# CH32V307RCT6-R1.net
KiCad netlist of a schematic drawn in Altium Designer
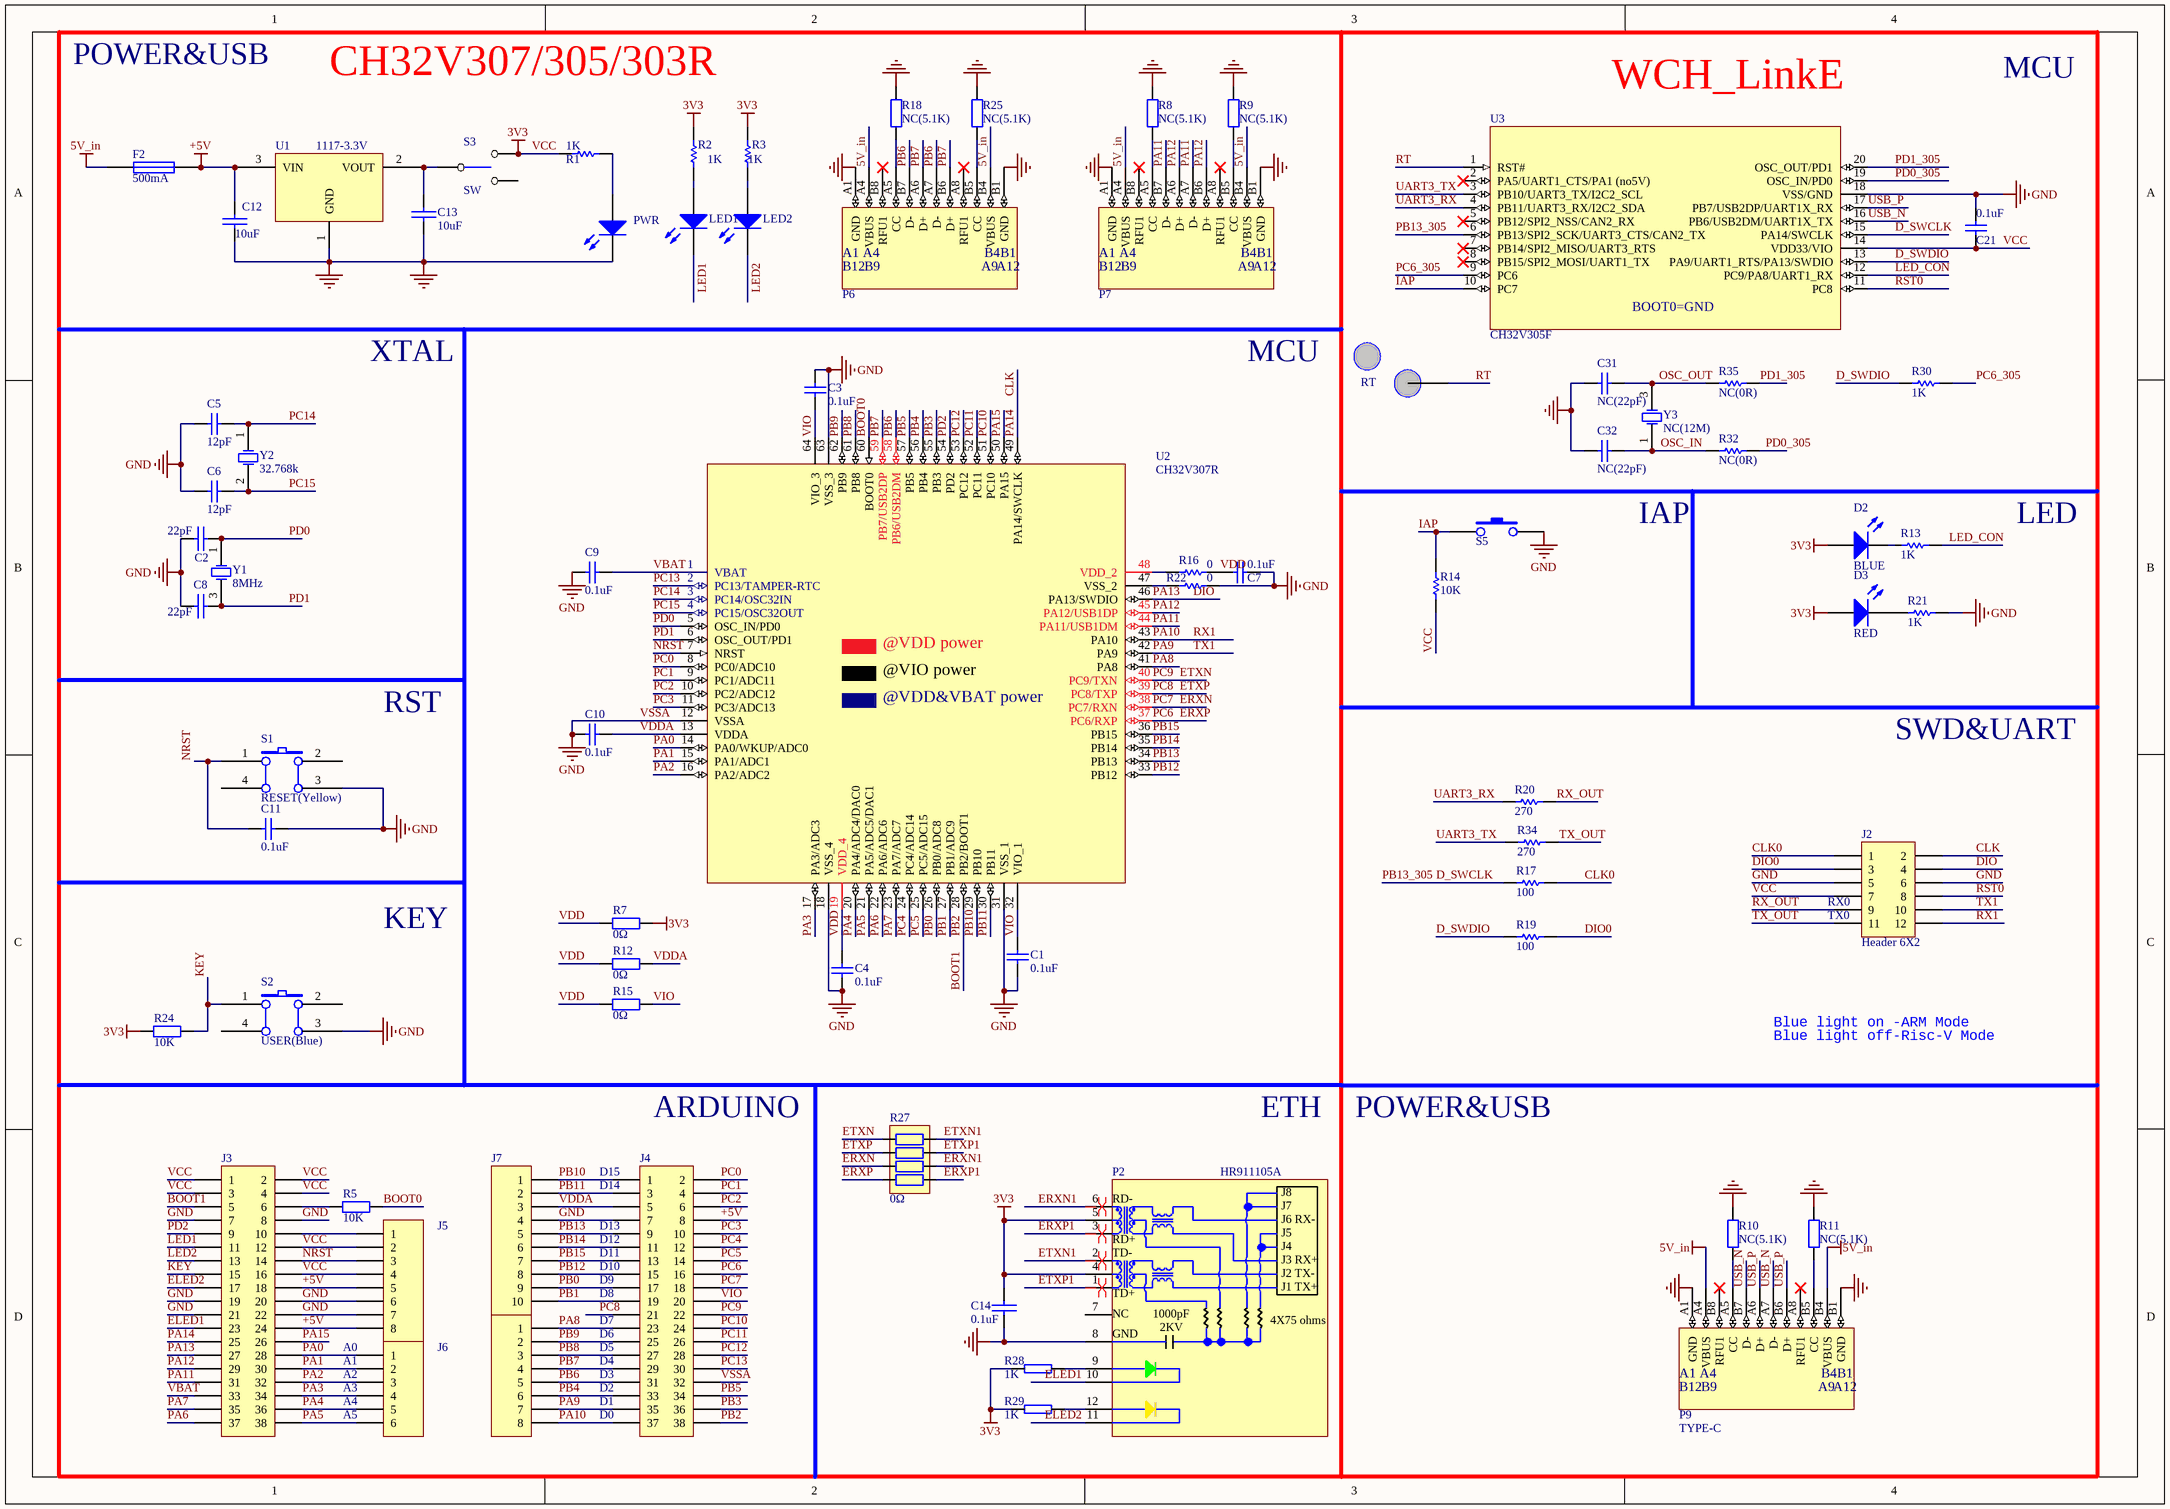
[diagram p0: CH32V307RCT6-R1.SchDoc]

(export (version "E")
  (design (tool "Eeschema 10.0.6"))
  (components
    (comp (ref "C1")
      (value "0.1uF")
      (footprint "0603_C")
      (description "Capacitor")
      (libsource (lib "Miscellaneous Devices") (part "Cap"))
    )
    (comp (ref "C2")
      (value "22pF")
      (footprint "0603_C")
      (description "Capacitor")
      (libsource (lib "*") (part "CAP"))
    )
    (comp (ref "C3")
      (value "0.1uF")
      (footprint "0603_C")
      (description "Capacitor")
      (libsource (lib "Miscellaneous Devices") (part "Cap"))
    )
    (comp (ref "C4")
      (value "0.1uF")
      (footprint "0603_C")
      (description "Capacitor")
      (libsource (lib "Miscellaneous Devices") (part "Cap"))
    )
    (comp (ref "C5")
      (value "12pF")
      (footprint "0603_C")
      (description "Capacitor")
      (libsource (lib "Miscellaneous Devices") (part "Cap"))
    )
    (comp (ref "C6")
      (value "12pF")
      (footprint "0603_C")
      (description "Capacitor")
      (libsource (lib "Miscellaneous Devices") (part "Cap"))
    )
    (comp (ref "C7")
      (value "0.1uF")
      (footprint "0603_C")
      (description "Capacitor")
      (libsource (lib "Miscellaneous Devices") (part "Cap"))
    )
    (comp (ref "C8")
      (value "22pF")
      (footprint "0603_C")
      (description "Capacitor")
      (libsource (lib "*") (part "CAP"))
    )
    (comp (ref "C9")
      (value "0.1uF")
      (footprint "0603_C")
      (description "Capacitor")
      (libsource (lib "Miscellaneous Devices") (part "Cap"))
    )
    (comp (ref "C10")
      (value "0.1uF")
      (footprint "0603_C")
      (description "Capacitor")
      (libsource (lib "Miscellaneous Devices") (part "Cap"))
    )
    (comp (ref "C11")
      (value "0.1uF")
      (footprint "0603_C")
      (description "Capacitor")
      (libsource (lib "Miscellaneous Devices") (part "Cap"))
    )
    (comp (ref "C12")
      (value "10uF")
      (footprint "3216_C")
      (description "Capacitor")
      (libsource (lib "*") (part "CAP"))
    )
    (comp (ref "C13")
      (value "10uF")
      (footprint "3216_C")
      (description "Capacitor")
      (libsource (lib "*") (part "CAP"))
    )
    (comp (ref "C14")
      (value "0.1uF")
      (footprint "0603_C")
      (description "Capacitor")
      (libsource (lib "*") (part "CAP"))
    )
    (comp (ref "C21")
      (value "0.1uF")
      (footprint "0603_C")
      (description "Capacitor")
      (libsource (lib "Miscellaneous Devices") (part "Cap"))
    )
    (comp (ref "C31")
      (value "NC(22pF)")
      (footprint "0603_C")
      (description "Capacitor")
      (fields (field (name "PUBLISHER") "Altium Limited"))
      (libsource (lib "*") (part "Cap"))
    )
    (comp (ref "C32")
      (value "NC(22pF)")
      (footprint "0603_C")
      (description "Capacitor")
      (fields (field (name "PUBLISHER") "Altium Limited"))
      (libsource (lib "*") (part "Cap"))
    )
    (comp (ref "D2")
      (value "BLUE")
      (footprint "0603+")
      (description "Typical RED, GREEN, YELLOW, AMBER GaAs LED")
      (fields (field (name "PUBLISHER") "Altium Limited"))
      (libsource (lib "MYLIB") (part "D0603"))
    )
    (comp (ref "D3")
      (value "RED")
      (footprint "0603+")
      (description "Typical RED, GREEN, YELLOW, AMBER GaAs LED")
      (fields (field (name "PUBLISHER") "Altium Limited"))
      (libsource (lib "MYLIB") (part "D0603"))
    )
    (comp (ref "F2")
      (value "500mA")
      (footprint "0805")
      (description "Fuse")
      (libsource (lib "*") (part "FUSE1"))
    )
    (comp (ref "J2")
      (value "Header 6X2")
      (footprint "IDC12-2.54mm")
      (description "Header, 6-Pin, Dual row")
      (fields (field (name "PUBLISHER") "Altium Limited"))
      (libsource (lib "Miscellaneous Connectors") (part "Header 6X2"))
    )
    (comp (ref "J3")
      (value "Header 19X2")
      (footprint "IDC38-2.54mm")
      (description "Header, 19-Pin, Dual row")
      (fields (field (name "PUBLISHER") "Altium Limited"))
      (libsource (lib "Miscellaneous Connectors") (part "Header 19X2"))
    )
    (comp (ref "J4")
      (value "Header 19X2")
      (footprint "IDC38-2.54mm")
      (description "Header, 19-Pin, Dual row")
      (fields (field (name "PUBLISHER") "Altium Limited"))
      (libsource (lib "Miscellaneous Connectors") (part "Header 19X2"))
    )
    (comp (ref "J5")
      (value "Header 8")
      (footprint "SIP8-2.54mm")
      (description "Header, 8-Pin")
      (fields (field (name "PUBLISHER") "Altium Limited"))
      (libsource (lib "Miscellaneous Connectors") (part "Header 8"))
    )
    (comp (ref "J6")
      (value "Header 6")
      (footprint "SIP6-2.54MM")
      (description "Header, 6-Pin")
      (fields (field (name "PUBLISHER") "Altium Limited"))
      (libsource (lib "Miscellaneous Connectors") (part "Header 6"))
    )
    (comp (ref "J7")
      (value "Header 10")
      (footprint "SIP10-2.54mm")
      (description "Header, 10-Pin")
      (fields (field (name "PUBLISHER") "Altium Limited"))
      (libsource (lib "Miscellaneous Connectors") (part "Header 10"))
    )
    (comp (ref "J8")
      (value "Header 8")
      (footprint "SIP8-2.54mm")
      (description "Header, 8-Pin")
      (fields (field (name "PUBLISHER") "Altium Limited"))
      (libsource (lib "") (part "Header 8_1"))
    )
    (comp (ref "LED1")
      (value "LED1   blue")
      (footprint "0603+")
      (description "Typical INFRARED GaAs LED")
      (fields (field (name "PUBLISHER") "Altium Limited"))
      (libsource (lib "Miscellaneous Devices") (part "LED0"))
    )
    (comp (ref "LED2")
      (value "LED2  blue")
      (footprint "0603+")
      (description "Typical INFRARED GaAs LED")
      (fields (field (name "PUBLISHER") "Altium Limited"))
      (libsource (lib "Miscellaneous Devices") (part "LED0"))
    )
    (comp (ref "P2") (value "HR911105A") (footprint "HR911105A") (libsource (lib "*") (part "HR911105A")))
    (comp (ref "P6")
      (value "TYPE-C")
      (footprint "TYPE-C-Receptacle-2.0")
      (libsource (lib "*") (part "TYPE-C1"))
    )
    (comp (ref "P7")
      (value "TYPE-C")
      (footprint "TYPE-C-Receptacle-2.0")
      (libsource (lib "*") (part "TYPE-C1"))
    )
    (comp (ref "P9")
      (value "TYPE-C")
      (footprint "TYPE-C-Receptacle-2.0")
      (libsource (lib "*") (part "TYPE-C1"))
    )
    (comp (ref "PWR")
      (value "POWER  red")
      (footprint "0603+")
      (description "Typical INFRARED GaAs LED")
      (fields (field (name "PUBLISHER") "Altium Limited"))
      (libsource (lib "Miscellaneous Devices") (part "LED0"))
    )
    (comp (ref "R1")
      (value "1K")
      (footprint "0603")
      (description "Semiconductor Resistor")
      (libsource (lib "Miscellaneous Devices") (part "Res Semi"))
    )
    (comp (ref "R2")
      (value "1K")
      (footprint "0603")
      (description "Semiconductor Resistor")
      (libsource (lib "Miscellaneous Devices") (part "Res Semi"))
    )
    (comp (ref "R3")
      (value "1K")
      (footprint "0603")
      (description "Semiconductor Resistor")
      (libsource (lib "Miscellaneous Devices") (part "Res Semi"))
    )
    (comp (ref "R5")
      (value "10K")
      (footprint "0603")
      (description "Resistor")
      (libsource (lib "") (part "Res2_3"))
    )
    (comp (ref "R7")
      (value "0Ω")
      (footprint "0603")
      (description "Resistor")
      (libsource (lib "") (part "Res2_2"))
    )
    (comp (ref "R8")
      (value "NC(5.1K)")
      (footprint "0603")
      (description "Resistor")
      (libsource (lib "") (part "Res2_1"))
    )
    (comp (ref "R9")
      (value "NC(5.1K)")
      (footprint "0603")
      (description "Resistor")
      (libsource (lib "") (part "Res2_1"))
    )
    (comp (ref "R10")
      (value "NC(5.1K)")
      (footprint "0603")
      (description "Resistor")
      (libsource (lib "Miscellaneous Devices") (part "Res2"))
    )
    (comp (ref "R11")
      (value "NC(5.1K)")
      (footprint "0603")
      (description "Resistor")
      (libsource (lib "Miscellaneous Devices") (part "Res2"))
    )
    (comp (ref "R12")
      (value "0Ω")
      (footprint "0603")
      (description "Resistor")
      (libsource (lib "") (part "Res2_2"))
    )
    (comp (ref "R13")
      (value "1K")
      (footprint "0603")
      (description "Resistor")
      (fields (field (name "PUBLISHER") "Altium Limited"))
      (libsource (lib "MYLIB") (part "0603-1"))
    )
    (comp (ref "R14")
      (value "10K")
      (footprint "0603")
      (description "Resistor")
      (fields (field (name "PUBLISHER") "Altium Limited"))
      (libsource (lib "MYLIB") (part "0603-1"))
    )
    (comp (ref "R15")
      (value "0Ω")
      (footprint "0603")
      (description "Resistor")
      (libsource (lib "") (part "Res2_2"))
    )
    (comp (ref "R16")
      (value "0")
      (footprint "0603")
      (description "Resistor")
      (fields (field (name "PUBLISHER") "Altium Limited"))
      (libsource (lib "MYLIB") (part "0603-1"))
    )
    (comp (ref "R17")
      (value "100")
      (footprint "0603")
      (description "Resistor")
      (fields (field (name "PUBLISHER") "Altium Limited"))
      (libsource (lib "MYLIB") (part "0603-1"))
    )
    (comp (ref "R18")
      (value "NC(5.1K)")
      (footprint "0603")
      (description "Resistor")
      (libsource (lib "") (part "Res2_1"))
    )
    (comp (ref "R19")
      (value "100")
      (footprint "0603")
      (description "Resistor")
      (fields (field (name "PUBLISHER") "Altium Limited"))
      (libsource (lib "MYLIB") (part "0603-1"))
    )
    (comp (ref "R20")
      (value "270")
      (footprint "0603")
      (description "Resistor")
      (fields (field (name "PUBLISHER") "Altium Limited"))
      (libsource (lib "MYLIB") (part "0603-1"))
    )
    (comp (ref "R21")
      (value "1K")
      (footprint "0603")
      (description "Resistor")
      (fields (field (name "PUBLISHER") "Altium Limited"))
      (libsource (lib "MYLIB") (part "0603-1"))
    )
    (comp (ref "R22")
      (value "0")
      (footprint "0603")
      (description "Resistor")
      (fields (field (name "PUBLISHER") "Altium Limited"))
      (libsource (lib "MYLIB") (part "0603-1"))
    )
    (comp (ref "R24")
      (value "10K")
      (footprint "0603")
      (description "Resistor")
      (libsource (lib "") (part "Res2_2"))
    )
    (comp (ref "R25")
      (value "NC(5.1K)")
      (footprint "0603")
      (description "Resistor")
      (libsource (lib "") (part "Res2_1"))
    )
    (comp (ref "R27")
      (value "0Ω")
      (footprint "8P4R-0603")
      (description "贴片网络排阻")
      (fields (field (name "版权归属") "源创客"))
      (libsource (lib "wch_sch_others") (part "R-8P4R"))
    )
    (comp (ref "R28") (value "1K") (footprint "0603") (libsource (lib "wch_sch_others") (part "RES")))
    (comp (ref "R29") (value "1K") (footprint "0603") (libsource (lib "wch_sch_others") (part "RES")))
    (comp (ref "R30")
      (value "1K")
      (footprint "0603")
      (description "Resistor")
      (fields (field (name "PUBLISHER") "Altium Limited"))
      (libsource (lib "MYLIB") (part "0603-1"))
    )
    (comp (ref "R32")
      (value "NC(0R)")
      (footprint "0603")
      (description "Resistor")
      (fields (field (name "PUBLISHER") "Altium Limited"))
      (libsource (lib "MYLIB") (part "0603-1"))
    )
    (comp (ref "R34")
      (value "270")
      (footprint "0603")
      (description "Resistor")
      (fields (field (name "PUBLISHER") "Altium Limited"))
      (libsource (lib "MYLIB") (part "0603-1"))
    )
    (comp (ref "R35")
      (value "NC(0R)")
      (footprint "0603")
      (description "Resistor")
      (fields (field (name "PUBLISHER") "Altium Limited"))
      (libsource (lib "MYLIB") (part "0603-1"))
    )
    (comp (ref "RT")
      (value "Testpoint")
      (footprint "TESTPOINT1")
      (description "测试点")
      (libsource (lib "wch_sch_others") (part "Testpoint"))
    )
    (comp (ref "S1")
      (value "RESET(Yellow)")
      (footprint "KEYX")
      (description "SE PUSHBUTTON")
      (libsource (lib "Documents") (part "SW PUSHBUTTON"))
    )
    (comp (ref "S2")
      (value "USER(Blue)")
      (footprint "KEYX")
      (description "SE PUSHBUTTON")
      (libsource (lib "Documents") (part "SW PUSHBUTTON"))
    )
    (comp (ref "S3") (value "SW") (footprint "SW1") (libsource (lib "MYSCH") (part "SW")))
    (comp (ref "S5") (value "KEY") (footprint "贴片按键") (libsource (lib "*") (part "KEY")))
    (comp (ref "U1")
      (value "1117-3.3V")
      (footprint "SOT-223")
      (libsource (lib "wch_sch_others") (part "1117-3.3V"))
    )
    (comp (ref "U2")
      (value "CH32V307R")
      (footprint "LQFP64M_10x10")
      (description "RISC-V FPU HD-MCU, 144MHz, USB_480M, USB OTG, 1000M Ethernet MAC, 2*CAN")
      (libsource (lib "CHXXX") (part "CH32V307R"))
    )
    (comp (ref "U3")
      (value "CH32V305F")
      (footprint "TSSOP20")
      (description "RISC-V FPU HD-MCU, 144MHz, USB_480M, CAN, UART*2, SPI")
      (libsource (lib "CHXXX") (part "CH32V305F"))
    )
    (comp (ref "Y1")
      (value "8MHz")
      (footprint "XT3225")
      (description "Crystal Oscillator")
      (fields (field (name "PUBLISHER") "Altium Limited"))
      (libsource (lib "*") (part "XTAL"))
    )
    (comp (ref "Y2")
      (value "32.768k")
      (footprint "FC-135")
      (description "Crystal Oscillator")
      (fields (field (name "PUBLISHER") "Altium Limited"))
      (libsource (lib "Miscellaneous Devices") (part "XTAL"))
    )
    (comp (ref "Y3")
      (value "NC(12M)")
      (footprint "XT3225")
      (description "Crystal Oscillator")
      (libsource (lib "*") (part "XTAL"))
    )
  )
  (nets
    (net (code "1") (name "+5V") (class "Default")
      (node (ref "C12") (pin "1") (pinfunction "1_1") (pintype "passive"))
      (node (ref "F2") (pin "2") (pinfunction "2_2") (pintype "passive"))
      (node (ref "J3") (pin "18") (pinfunction "18_18") (pintype "passive"))
      (node (ref "J3") (pin "24") (pinfunction "24_24") (pintype "passive"))
      (node (ref "J4") (pin "8") (pinfunction "8_8") (pintype "passive"))
      (node (ref "J5") (pin "5") (pinfunction "5_5") (pintype "passive"))
      (node (ref "J5") (pin "8") (pinfunction "8_8") (pintype "passive"))
      (node (ref "U1") (pin "3") (pinfunction "VIN_3") (pintype "passive"))
    )
    (net (code "2") (name "/BOOT0") (class "Default")
      (node (ref "R5") (pin "2") (pinfunction "2_2") (pintype "passive"))
      (node (ref "U2") (pin "60") (pinfunction "BOOT0_60") (pintype "input"))
    )
    (net (code "3") (name "/BOOT1") (class "Default")
      (node (ref "J3") (pin "5") (pinfunction "5_5") (pintype "passive"))
      (node (ref "J4") (pin "38") (pinfunction "38_38") (pintype "passive"))
      (node (ref "U2") (pin "28") (pinfunction "PB2/BOOT1_28") (pintype "bidirectional"))
    )
    (net (code "4") (name "/CLK") (class "Default")
      (node (ref "J2") (pin "2") (pinfunction "2_2") (pintype "passive"))
      (node (ref "J3") (pin "25") (pinfunction "25_25") (pintype "passive"))
      (node (ref "U2") (pin "49") (pinfunction "PA14/SWCLK_49") (pintype "bidirectional"))
    )
    (net (code "5") (name "/CLK0") (class "Default")
      (node (ref "J2") (pin "1") (pinfunction "1_1") (pintype "passive"))
      (node (ref "R17") (pin "1") (pinfunction "1_1") (pintype "passive"))
    )
    (net (code "6") (name "/DIO") (class "Default")
      (node (ref "J2") (pin "4") (pinfunction "4_4") (pintype "passive"))
      (node (ref "J3") (pin "27") (pinfunction "27_27") (pintype "passive"))
      (node (ref "U2") (pin "46") (pinfunction "PA13/SWDIO_46") (pintype "bidirectional"))
    )
    (net (code "7") (name "/DIO0") (class "Default")
      (node (ref "J2") (pin "3") (pinfunction "3_3") (pintype "passive"))
      (node (ref "R19") (pin "1") (pinfunction "1_1") (pintype "passive"))
    )
    (net (code "8") (name "/D_SWCLK") (class "Default")
      (node (ref "R17") (pin "2") (pinfunction "2_2") (pintype "passive"))
      (node (ref "U3") (pin "15") (pinfunction "PA14/SWCLK_15") (pintype "bidirectional"))
      (node (ref "U3") (pin "6") (pinfunction "PB13/SPI2_SCK/UART3_CTS/CAN2_TX_6") (pintype "bidirectional"))
    )
    (net (code "9") (name "/D_SWDIO") (class "Default")
      (node (ref "R19") (pin "2") (pinfunction "2_2") (pintype "passive"))
      (node (ref "R30") (pin "1") (pinfunction "1_1") (pintype "passive"))
      (node (ref "U3") (pin "13") (pinfunction "PA9/UART1_RTS/PA13/SWDIO_13") (pintype "bidirectional"))
    )
    (net (code "10") (name "/ELED1") (class "Default")
      (node (ref "J3") (pin "23") (pinfunction "23_23") (pintype "passive"))
      (node (ref "P2") (pin "10") (pintype "passive"))
    )
    (net (code "11") (name "/ELED2") (class "Default")
      (node (ref "J3") (pin "17") (pinfunction "17_17") (pintype "passive"))
      (node (ref "P2") (pin "11") (pintype "passive"))
    )
    (net (code "12") (name "/ERXN") (class "Default")
      (node (ref "J4") (pin "18") (pinfunction "18_18") (pintype "passive"))
      (node (ref "R27") (pin "3") (pinfunction "3_3") (pintype "passive"))
      (node (ref "U2") (pin "38") (pinfunction "PC7/RXN_38") (pintype "bidirectional"))
    )
    (net (code "13") (name "/ERXN1") (class "Default")
      (node (ref "P2") (pin "6") (pintype "passive"))
      (node (ref "R27") (pin "6") (pinfunction "6_6") (pintype "passive"))
    )
    (net (code "14") (name "/ERXP") (class "Default")
      (node (ref "J4") (pin "16") (pinfunction "16_16") (pintype "passive"))
      (node (ref "R27") (pin "4") (pinfunction "4_4") (pintype "passive"))
      (node (ref "U2") (pin "37") (pinfunction "PC6/RXP_37") (pintype "bidirectional"))
    )
    (net (code "15") (name "/ERXP1") (class "Default")
      (node (ref "P2") (pin "3") (pintype "passive"))
      (node (ref "R27") (pin "5") (pinfunction "5_5") (pintype "passive"))
    )
    (net (code "16") (name "/ETXN") (class "Default")
      (node (ref "J4") (pin "22") (pinfunction "22_22") (pintype "passive"))
      (node (ref "R27") (pin "1") (pinfunction "1_1") (pintype "passive"))
      (node (ref "U2") (pin "40") (pinfunction "PC9/TXN_40") (pintype "bidirectional"))
    )
    (net (code "17") (name "/ETXN1") (class "Default")
      (node (ref "P2") (pin "2") (pintype "passive"))
      (node (ref "R27") (pin "8") (pinfunction "8_8") (pintype "passive"))
    )
    (net (code "18") (name "/ETXP") (class "Default")
      (node (ref "J4") (pin "21") (pinfunction "21_21") (pintype "passive"))
      (node (ref "R27") (pin "2") (pinfunction "2_2") (pintype "passive"))
      (node (ref "U2") (pin "39") (pinfunction "PC8/TXP_39") (pintype "bidirectional"))
    )
    (net (code "19") (name "/ETXP1") (class "Default")
      (node (ref "P2") (pin "1") (pintype "passive"))
      (node (ref "R27") (pin "7") (pinfunction "7_7") (pintype "passive"))
    )
    (net (code "20") (name "/IAP") (class "Default")
      (node (ref "R14") (pin "1") (pinfunction "1_1") (pintype "passive"))
      (node (ref "S5") (pin "1") (pinfunction "1_1") (pintype "passive"))
      (node (ref "U3") (pin "10") (pinfunction "PC7_10") (pintype "bidirectional"))
    )
    (net (code "21") (name "/KEY") (class "Default")
      (node (ref "J3") (pin "15") (pinfunction "15_15") (pintype "passive"))
      (node (ref "R24") (pin "1") (pinfunction "1_1") (pintype "passive"))
      (node (ref "S2") (pin "1") (pinfunction "A0_1") (pintype "passive"))
    )
    (net (code "22") (name "/LED1") (class "Default")
      (node (ref "J3") (pin "11") (pinfunction "11_11") (pintype "passive"))
      (node (ref "LED1") (pin "2") (pinfunction "K_2") (pintype "passive"))
    )
    (net (code "23") (name "/LED2") (class "Default")
      (node (ref "J3") (pin "13") (pinfunction "13_13") (pintype "passive"))
      (node (ref "LED2") (pin "2") (pinfunction "K_2") (pintype "passive"))
    )
    (net (code "24") (name "/LED_CON") (class "Default")
      (node (ref "R13") (pin "1") (pinfunction "1_1") (pintype "passive"))
      (node (ref "U3") (pin "12") (pinfunction "PC9/PA8/UART1_RX_12") (pintype "bidirectional"))
    )
    (net (code "25") (name "/NRST") (class "Default")
      (node (ref "C11") (pin "2") (pinfunction "2_2") (pintype "passive"))
      (node (ref "J3") (pin "14") (pinfunction "14_14") (pintype "passive"))
      (node (ref "J5") (pin "3") (pinfunction "3_3") (pintype "passive"))
      (node (ref "S1") (pin "1") (pinfunction "A0_1") (pintype "passive"))
      (node (ref "U2") (pin "7") (pinfunction "NRST_7") (pintype "input"))
    )
    (net (code "26") (name "/OSC_IN") (class "Default")
      (node (ref "C32") (pin "2") (pinfunction "2_2") (pintype "passive"))
      (node (ref "R32") (pin "2") (pinfunction "2_2") (pintype "passive"))
      (node (ref "Y3") (pin "1") (pinfunction "OSC1_1") (pintype "passive"))
    )
    (net (code "27") (name "/OSC_OUT") (class "Default")
      (node (ref "C31") (pin "2") (pinfunction "2_2") (pintype "passive"))
      (node (ref "R35") (pin "2") (pinfunction "2_2") (pintype "passive"))
      (node (ref "Y3") (pin "3") (pinfunction "OSC2_3") (pintype "passive"))
    )
    (net (code "28") (name "/PA0") (class "Default")
      (node (ref "J3") (pin "28") (pinfunction "28_28") (pintype "passive"))
      (node (ref "J6") (pin "1") (pinfunction "1_1") (pintype "passive"))
      (node (ref "U2") (pin "14") (pinfunction "PA0/WKUP/ADC0_14") (pintype "bidirectional"))
    )
    (net (code "29") (name "/PA1") (class "Default")
      (node (ref "J3") (pin "30") (pinfunction "30_30") (pintype "passive"))
      (node (ref "J6") (pin "2") (pinfunction "2_2") (pintype "passive"))
      (node (ref "U2") (pin "15") (pinfunction "PA1/ADC1_15") (pintype "bidirectional"))
    )
    (net (code "30") (name "/PA2") (class "Default")
      (node (ref "J3") (pin "32") (pinfunction "32_32") (pintype "passive"))
      (node (ref "J6") (pin "3") (pinfunction "3_3") (pintype "passive"))
      (node (ref "U2") (pin "16") (pinfunction "PA2/ADC2_16") (pintype "bidirectional"))
    )
    (net (code "31") (name "/PA3") (class "Default")
      (node (ref "J3") (pin "34") (pinfunction "34_34") (pintype "passive"))
      (node (ref "J6") (pin "4") (pinfunction "4_4") (pintype "passive"))
      (node (ref "U2") (pin "17") (pinfunction "PA3/ADC3_17") (pintype "bidirectional"))
    )
    (net (code "32") (name "/PA4") (class "Default")
      (node (ref "J3") (pin "36") (pinfunction "36_36") (pintype "passive"))
      (node (ref "J6") (pin "5") (pinfunction "5_5") (pintype "passive"))
      (node (ref "U2") (pin "20") (pinfunction "PA4/ADC4/DAC0_20") (pintype "bidirectional"))
    )
    (net (code "33") (name "/PA5") (class "Default")
      (node (ref "J3") (pin "38") (pinfunction "38_38") (pintype "passive"))
      (node (ref "J6") (pin "6") (pinfunction "6_6") (pintype "passive"))
      (node (ref "U2") (pin "21") (pinfunction "PA5/ADC5/DAC1_21") (pintype "bidirectional"))
    )
    (net (code "34") (name "/PA6") (class "Default")
      (node (ref "J3") (pin "37") (pinfunction "37_37") (pintype "passive"))
      (node (ref "U2") (pin "22") (pinfunction "PA6/ADC6_22") (pintype "bidirectional"))
    )
    (net (code "35") (name "/PA7") (class "Default")
      (node (ref "J3") (pin "35") (pinfunction "35_35") (pintype "passive"))
      (node (ref "U2") (pin "23") (pinfunction "PA7/ADC7_23") (pintype "bidirectional"))
    )
    (net (code "36") (name "/PA8") (class "Default")
      (node (ref "J4") (pin "23") (pinfunction "23_23") (pintype "passive"))
      (node (ref "J8") (pin "1") (pinfunction "1_1") (pintype "passive"))
      (node (ref "U2") (pin "41") (pinfunction "PA8_41") (pintype "bidirectional"))
    )
    (net (code "37") (name "/PA9") (class "Default")
      (node (ref "J2") (pin "10") (pinfunction "10_10") (pintype "passive"))
      (node (ref "J4") (pin "35") (pinfunction "35_35") (pintype "passive"))
      (node (ref "J8") (pin "7") (pinfunction "7_7") (pintype "passive"))
      (node (ref "U2") (pin "42") (pinfunction "PA9_42") (pintype "bidirectional"))
    )
    (net (code "38") (name "/PA10") (class "Default")
      (node (ref "J2") (pin "12") (pinfunction "12_12") (pintype "passive"))
      (node (ref "J4") (pin "37") (pinfunction "37_37") (pintype "passive"))
      (node (ref "J8") (pin "8") (pinfunction "8_8") (pintype "passive"))
      (node (ref "U2") (pin "43") (pinfunction "PA10_43") (pintype "bidirectional"))
    )
    (net (code "39") (name "/PA11") (class "Default")
      (node (ref "J3") (pin "31") (pinfunction "31_31") (pintype "passive"))
      (node (ref "P7") (pin "A7") (pinfunction "D-_A7") (pintype "bidirectional"))
      (node (ref "P7") (pin "B7") (pinfunction "D-_B7") (pintype "bidirectional"))
      (node (ref "U2") (pin "44") (pinfunction "PA11/USB1DM_44") (pintype "bidirectional"))
    )
    (net (code "40") (name "/PA12") (class "Default")
      (node (ref "J3") (pin "29") (pinfunction "29_29") (pintype "passive"))
      (node (ref "P7") (pin "A6") (pinfunction "D+_A6") (pintype "bidirectional"))
      (node (ref "P7") (pin "B6") (pinfunction "D+_B6") (pintype "bidirectional"))
      (node (ref "U2") (pin "45") (pinfunction "PA12/USB1DP_45") (pintype "bidirectional"))
    )
    (net (code "41") (name "/PA15") (class "Default")
      (node (ref "J3") (pin "26") (pinfunction "26_26") (pintype "passive"))
      (node (ref "U2") (pin "50") (pinfunction "PA15_50") (pintype "bidirectional"))
    )
    (net (code "42") (name "/PB0") (class "Default")
      (node (ref "J4") (pin "17") (pinfunction "17_17") (pintype "passive"))
      (node (ref "J7") (pin "9") (pinfunction "9_9") (pintype "passive"))
      (node (ref "U2") (pin "26") (pinfunction "PB0/ADC8_26") (pintype "bidirectional"))
    )
    (net (code "43") (name "/PB1") (class "Default")
      (node (ref "J4") (pin "19") (pinfunction "19_19") (pintype "passive"))
      (node (ref "J7") (pin "10") (pinfunction "10_10") (pintype "passive"))
      (node (ref "U2") (pin "27") (pinfunction "PB1/ADC9_27") (pintype "bidirectional"))
    )
    (net (code "44") (name "/PB3") (class "Default")
      (node (ref "J4") (pin "36") (pinfunction "36_36") (pintype "passive"))
      (node (ref "U2") (pin "55") (pinfunction "PB3_55") (pintype "bidirectional"))
    )
    (net (code "45") (name "/PB4") (class "Default")
      (node (ref "J4") (pin "33") (pinfunction "33_33") (pintype "passive"))
      (node (ref "J8") (pin "6") (pinfunction "6_6") (pintype "passive"))
      (node (ref "U2") (pin "56") (pinfunction "PB4_56") (pintype "bidirectional"))
    )
    (net (code "46") (name "/PB5") (class "Default")
      (node (ref "J4") (pin "34") (pinfunction "34_34") (pintype "passive"))
      (node (ref "U2") (pin "57") (pinfunction "PB5_57") (pintype "bidirectional"))
    )
    (net (code "47") (name "/PB6") (class "Default")
      (node (ref "J4") (pin "31") (pinfunction "31_31") (pintype "passive"))
      (node (ref "J8") (pin "5") (pinfunction "5_5") (pintype "passive"))
      (node (ref "P6") (pin "A7") (pinfunction "D-_A7") (pintype "bidirectional"))
      (node (ref "P6") (pin "B7") (pinfunction "D-_B7") (pintype "bidirectional"))
      (node (ref "U2") (pin "58") (pinfunction "PB6/USB2DM_58") (pintype "bidirectional"))
    )
    (net (code "48") (name "/PB7") (class "Default")
      (node (ref "J4") (pin "29") (pinfunction "29_29") (pintype "passive"))
      (node (ref "J8") (pin "4") (pinfunction "4_4") (pintype "passive"))
      (node (ref "P6") (pin "A6") (pinfunction "D+_A6") (pintype "bidirectional"))
      (node (ref "P6") (pin "B6") (pinfunction "D+_B6") (pintype "bidirectional"))
      (node (ref "U2") (pin "59") (pinfunction "PB7/USB2DP_59") (pintype "bidirectional"))
    )
    (net (code "49") (name "/PB8") (class "Default")
      (node (ref "J4") (pin "27") (pinfunction "27_27") (pintype "passive"))
      (node (ref "J8") (pin "3") (pinfunction "3_3") (pintype "passive"))
      (node (ref "U2") (pin "61") (pinfunction "PB8_61") (pintype "bidirectional"))
    )
    (net (code "50") (name "/PB9") (class "Default")
      (node (ref "J4") (pin "25") (pinfunction "25_25") (pintype "passive"))
      (node (ref "J8") (pin "2") (pinfunction "2_2") (pintype "passive"))
      (node (ref "U2") (pin "62") (pinfunction "PB9_62") (pintype "bidirectional"))
    )
    (net (code "51") (name "/PB10") (class "Default")
      (node (ref "J4") (pin "1") (pinfunction "1_1") (pintype "passive"))
      (node (ref "J7") (pin "1") (pinfunction "1_1") (pintype "passive"))
      (node (ref "U2") (pin "29") (pinfunction "PB10_29") (pintype "bidirectional"))
    )
    (net (code "52") (name "/PB11") (class "Default")
      (node (ref "J4") (pin "3") (pinfunction "3_3") (pintype "passive"))
      (node (ref "J7") (pin "2") (pinfunction "2_2") (pintype "passive"))
      (node (ref "U2") (pin "30") (pinfunction "PB11_30") (pintype "bidirectional"))
    )
    (net (code "53") (name "/PB12") (class "Default")
      (node (ref "J4") (pin "15") (pinfunction "15_15") (pintype "passive"))
      (node (ref "J7") (pin "8") (pinfunction "8_8") (pintype "passive"))
      (node (ref "U2") (pin "33") (pinfunction "PB12_33") (pintype "bidirectional"))
    )
    (net (code "54") (name "/PB13") (class "Default")
      (node (ref "J4") (pin "9") (pinfunction "9_9") (pintype "passive"))
      (node (ref "J7") (pin "5") (pinfunction "5_5") (pintype "passive"))
      (node (ref "U2") (pin "34") (pinfunction "PB13_34") (pintype "bidirectional"))
    )
    (net (code "55") (name "/PB14") (class "Default")
      (node (ref "J4") (pin "11") (pinfunction "11_11") (pintype "passive"))
      (node (ref "J7") (pin "6") (pinfunction "6_6") (pintype "passive"))
      (node (ref "U2") (pin "35") (pinfunction "PB14_35") (pintype "bidirectional"))
    )
    (net (code "56") (name "/PB15") (class "Default")
      (node (ref "J4") (pin "13") (pinfunction "13_13") (pintype "passive"))
      (node (ref "J7") (pin "7") (pinfunction "7_7") (pintype "passive"))
      (node (ref "U2") (pin "36") (pinfunction "PB15_36") (pintype "bidirectional"))
    )
    (net (code "57") (name "/PC0") (class "Default")
      (node (ref "J4") (pin "2") (pinfunction "2_2") (pintype "passive"))
      (node (ref "U2") (pin "8") (pinfunction "PC0/ADC10_8") (pintype "bidirectional"))
    )
    (net (code "58") (name "/PC1") (class "Default")
      (node (ref "J4") (pin "4") (pinfunction "4_4") (pintype "passive"))
      (node (ref "U2") (pin "9") (pinfunction "PC1/ADC11_9") (pintype "bidirectional"))
    )
    (net (code "59") (name "/PC2") (class "Default")
      (node (ref "J4") (pin "6") (pinfunction "6_6") (pintype "passive"))
      (node (ref "U2") (pin "10") (pinfunction "PC2/ADC12_10") (pintype "bidirectional"))
    )
    (net (code "60") (name "/PC3") (class "Default")
      (node (ref "J4") (pin "10") (pinfunction "10_10") (pintype "passive"))
      (node (ref "U2") (pin "11") (pinfunction "PC3/ADC13_11") (pintype "bidirectional"))
    )
    (net (code "61") (name "/PC4") (class "Default")
      (node (ref "J4") (pin "12") (pinfunction "12_12") (pintype "passive"))
      (node (ref "U2") (pin "24") (pinfunction "PC4/ADC14_24") (pintype "bidirectional"))
    )
    (net (code "62") (name "/PC5") (class "Default")
      (node (ref "J4") (pin "14") (pinfunction "14_14") (pintype "passive"))
      (node (ref "U2") (pin "25") (pinfunction "PC5/ADC15_25") (pintype "bidirectional"))
    )
    (net (code "63") (name "/PC6_305") (class "Default")
      (node (ref "R30") (pin "2") (pinfunction "2_2") (pintype "passive"))
      (node (ref "U3") (pin "9") (pinfunction "PC6_9") (pintype "bidirectional"))
    )
    (net (code "64") (name "/PC10") (class "Default")
      (node (ref "J4") (pin "24") (pinfunction "24_24") (pintype "passive"))
      (node (ref "U2") (pin "51") (pinfunction "PC10_51") (pintype "bidirectional"))
    )
    (net (code "65") (name "/PC11") (class "Default")
      (node (ref "J4") (pin "26") (pinfunction "26_26") (pintype "passive"))
      (node (ref "U2") (pin "52") (pinfunction "PC11_52") (pintype "bidirectional"))
    )
    (net (code "66") (name "/PC12") (class "Default")
      (node (ref "J4") (pin "28") (pinfunction "28_28") (pintype "passive"))
      (node (ref "U2") (pin "53") (pinfunction "PC12_53") (pintype "bidirectional"))
    )
    (net (code "67") (name "/PC13") (class "Default")
      (node (ref "J4") (pin "30") (pinfunction "30_30") (pintype "passive"))
      (node (ref "U2") (pin "2") (pinfunction "PC13/TAMPER-RTC_2") (pintype "bidirectional"))
    )
    (net (code "68") (name "/PC14") (class "Default")
      (node (ref "C5") (pin "1") (pinfunction "1_1") (pintype "passive"))
      (node (ref "U2") (pin "3") (pinfunction "PC14/OSC32IN_3") (pintype "bidirectional"))
      (node (ref "Y2") (pin "1") (pinfunction "OSC1_1") (pintype "passive"))
    )
    (net (code "69") (name "/PC15") (class "Default")
      (node (ref "C6") (pin "1") (pinfunction "1_1") (pintype "passive"))
      (node (ref "U2") (pin "4") (pinfunction "PC15/OSC32OUT_4") (pintype "bidirectional"))
      (node (ref "Y2") (pin "2") (pinfunction "OSC2_2") (pintype "passive"))
    )
    (net (code "70") (name "/PD0") (class "Default")
      (node (ref "C2") (pin "2") (pinfunction "2_2") (pintype "passive"))
      (node (ref "U2") (pin "5") (pinfunction "OSC_IN/PD0_5") (pintype "bidirectional"))
      (node (ref "Y1") (pin "1") (pinfunction "OSC1_1") (pintype "passive"))
    )
    (net (code "71") (name "/PD0_305") (class "Default")
      (node (ref "R32") (pin "1") (pinfunction "1_1") (pintype "passive"))
      (node (ref "U3") (pin "19") (pinfunction "OSC_IN/PD0_19") (pintype "bidirectional"))
    )
    (net (code "72") (name "/PD1") (class "Default")
      (node (ref "C8") (pin "2") (pinfunction "2_2") (pintype "passive"))
      (node (ref "U2") (pin "6") (pinfunction "OSC_OUT/PD1_6") (pintype "bidirectional"))
      (node (ref "Y1") (pin "3") (pinfunction "OSC2_3") (pintype "passive"))
    )
    (net (code "73") (name "/PD1_305") (class "Default")
      (node (ref "R35") (pin "1") (pinfunction "1_1") (pintype "passive"))
      (node (ref "U3") (pin "20") (pinfunction "OSC_OUT/PD1_20") (pintype "bidirectional"))
    )
    (net (code "74") (name "/PD2") (class "Default")
      (node (ref "J3") (pin "9") (pinfunction "9_9") (pintype "passive"))
      (node (ref "U2") (pin "54") (pinfunction "PD2_54") (pintype "bidirectional"))
    )
    (net (code "75") (name "/RST0") (class "Default")
      (node (ref "J2") (pin "8") (pinfunction "8_8") (pintype "passive"))
      (node (ref "U3") (pin "11") (pinfunction "PC8_11") (pintype "bidirectional"))
    )
    (net (code "76") (name "/RT") (class "Default")
      (node (ref "RT") (pin "1") (pinfunction "point_1") (pintype "passive"))
      (node (ref "U3") (pin "1") (pinfunction "RST#_1") (pintype "input"))
    )
    (net (code "77") (name "/RX_OUT") (class "Default")
      (node (ref "J2") (pin "9") (pinfunction "9_9") (pintype "passive"))
      (node (ref "R20") (pin "1") (pinfunction "1_1") (pintype "passive"))
    )
    (net (code "78") (name "/TX_OUT") (class "Default")
      (node (ref "J2") (pin "11") (pinfunction "11_11") (pintype "passive"))
      (node (ref "R34") (pin "1") (pinfunction "1_1") (pintype "passive"))
    )
    (net (code "79") (name "/UART3_RX") (class "Default")
      (node (ref "R20") (pin "2") (pinfunction "2_2") (pintype "passive"))
      (node (ref "U3") (pin "4") (pinfunction "PB11/UART3_RX/I2C2_SDA_4") (pintype "bidirectional"))
    )
    (net (code "80") (name "/UART3_TX") (class "Default")
      (node (ref "R34") (pin "2") (pinfunction "2_2") (pintype "passive"))
      (node (ref "U3") (pin "3") (pinfunction "PB10/UART3_TX/I2C2_SCL_3") (pintype "bidirectional"))
    )
    (net (code "81") (name "/USB_N") (class "Default")
      (node (ref "P9") (pin "A7") (pinfunction "D-_A7") (pintype "bidirectional"))
      (node (ref "P9") (pin "B7") (pinfunction "D-_B7") (pintype "bidirectional"))
      (node (ref "U3") (pin "16") (pinfunction "PB6/USB2DM/UART1X_TX_16") (pintype "bidirectional"))
    )
    (net (code "82") (name "/USB_P") (class "Default")
      (node (ref "P9") (pin "A6") (pinfunction "D+_A6") (pintype "bidirectional"))
      (node (ref "P9") (pin "B6") (pinfunction "D+_B6") (pintype "bidirectional"))
      (node (ref "U3") (pin "17") (pinfunction "PB7/USB2DP/UART1X_RX_17") (pintype "bidirectional"))
    )
    (net (code "83") (name "/VBAT") (class "Default")
      (node (ref "C9") (pin "1") (pinfunction "1_1") (pintype "passive"))
      (node (ref "J3") (pin "33") (pinfunction "33_33") (pintype "passive"))
      (node (ref "U2") (pin "1") (pinfunction "VBAT_1") (pintype "power_in"))
    )
    (net (code "84") (name "/VDD") (class "Default")
      (node (ref "C4") (pin "2") (pinfunction "2_2") (pintype "passive"))
      (node (ref "C7") (pin "2") (pinfunction "2_2") (pintype "passive"))
      (node (ref "R12") (pin "2") (pinfunction "2_2") (pintype "passive"))
      (node (ref "R15") (pin "2") (pinfunction "2_2") (pintype "passive"))
      (node (ref "R16") (pin "1") (pinfunction "1_1") (pintype "passive"))
      (node (ref "R7") (pin "2") (pinfunction "2_2") (pintype "passive"))
      (node (ref "U2") (pin "19") (pinfunction "VDD_4_19") (pintype "power_in"))
    )
    (net (code "85") (name "/VDDA") (class "Default")
      (node (ref "C10") (pin "1") (pinfunction "1_1") (pintype "passive"))
      (node (ref "J4") (pin "5") (pinfunction "5_5") (pintype "passive"))
      (node (ref "J7") (pin "3") (pinfunction "3_3") (pintype "passive"))
      (node (ref "R12") (pin "1") (pinfunction "1_1") (pintype "passive"))
      (node (ref "U2") (pin "13") (pinfunction "VDDA_13") (pintype "power_in"))
    )
    (net (code "86") (name "/VIO") (class "Default")
      (node (ref "C1") (pin "2") (pinfunction "2_2") (pintype "passive"))
      (node (ref "C3") (pin "2") (pinfunction "2_2") (pintype "passive"))
      (node (ref "J4") (pin "20") (pinfunction "20_20") (pintype "passive"))
      (node (ref "R15") (pin "1") (pinfunction "1_1") (pintype "passive"))
      (node (ref "U2") (pin "32") (pinfunction "VIO_1_32") (pintype "power_in"))
      (node (ref "U2") (pin "64") (pinfunction "VIO_3_64") (pintype "power_in"))
    )
    (net (code "87") (name "3V3") (class "Default")
      (node (ref "C14") (pin "2") (pinfunction "2_2") (pintype "passive"))
      (node (ref "C21") (pin "1") (pinfunction "1_1") (pintype "passive"))
      (node (ref "D2") (pin "1") (pinfunction "A_1") (pintype "passive"))
      (node (ref "D3") (pin "1") (pinfunction "A_1") (pintype "passive"))
      (node (ref "J2") (pin "7") (pinfunction "7_7") (pintype "passive"))
      (node (ref "J3") (pin "1") (pinfunction "1_1") (pintype "passive"))
      (node (ref "J3") (pin "12") (pinfunction "12_12") (pintype "passive"))
      (node (ref "J3") (pin "16") (pinfunction "16_16") (pintype "passive"))
      (node (ref "J3") (pin "2") (pinfunction "2_2") (pintype "passive"))
      (node (ref "J3") (pin "3") (pinfunction "3_3") (pintype "passive"))
      (node (ref "J3") (pin "4") (pinfunction "4_4") (pintype "passive"))
      (node (ref "J5") (pin "2") (pinfunction "2_2") (pintype "passive"))
      (node (ref "J5") (pin "4") (pinfunction "4_4") (pintype "passive"))
      (node (ref "P2") (pin "4") (pintype "passive"))
      (node (ref "P2") (pin "5") (pintype "passive"))
      (node (ref "R1") (pin "2") (pinfunction "2_2") (pintype "passive"))
      (node (ref "R14") (pin "2") (pinfunction "2_2") (pintype "passive"))
      (node (ref "R2") (pin "1") (pinfunction "1_1") (pintype "passive"))
      (node (ref "R24") (pin "2") (pinfunction "2_2") (pintype "passive"))
      (node (ref "R28") (pin "1") (pintype "passive"))
      (node (ref "R29") (pin "1") (pintype "passive"))
      (node (ref "R3") (pin "1") (pinfunction "1_1") (pintype "passive"))
      (node (ref "R7") (pin "1") (pinfunction "1_1") (pintype "passive"))
      (node (ref "S3") (pin "3") (pinfunction "3_3") (pintype "passive"))
      (node (ref "U3") (pin "14") (pinfunction "VDD33/VIO_14") (pintype "power_in"))
    )
    (net (code "88") (name "5V_in") (class "Default")
      (node (ref "F2") (pin "1") (pinfunction "1_1") (pintype "passive"))
      (node (ref "P6") (pin "A4") (pinfunction "VBUS_A4") (pintype "bidirectional"))
      (node (ref "P6") (pin "B4") (pinfunction "VBUS_B4") (pintype "bidirectional"))
      (node (ref "P7") (pin "A4") (pinfunction "VBUS_A4") (pintype "bidirectional"))
      (node (ref "P7") (pin "B4") (pinfunction "VBUS_B4") (pintype "bidirectional"))
      (node (ref "P9") (pin "A4") (pinfunction "VBUS_A4") (pintype "bidirectional"))
      (node (ref "P9") (pin "B4") (pinfunction "VBUS_B4") (pintype "bidirectional"))
    )
    (net (code "89") (name "GND") (class "Default")
      (node (ref "C1") (pin "1") (pinfunction "1_1") (pintype "passive"))
      (node (ref "C10") (pin "2") (pinfunction "2_2") (pintype "passive"))
      (node (ref "C11") (pin "1") (pinfunction "1_1") (pintype "passive"))
      (node (ref "C12") (pin "2") (pinfunction "2_2") (pintype "passive"))
      (node (ref "C13") (pin "2") (pinfunction "2_2") (pintype "passive"))
      (node (ref "C14") (pin "1") (pinfunction "1_1") (pintype "passive"))
      (node (ref "C2") (pin "1") (pinfunction "1_1") (pintype "passive"))
      (node (ref "C21") (pin "2") (pinfunction "2_2") (pintype "passive"))
      (node (ref "C3") (pin "1") (pinfunction "1_1") (pintype "passive"))
      (node (ref "C31") (pin "1") (pinfunction "1_1") (pintype "passive"))
      (node (ref "C32") (pin "1") (pinfunction "1_1") (pintype "passive"))
      (node (ref "C4") (pin "1") (pinfunction "1_1") (pintype "passive"))
      (node (ref "C5") (pin "2") (pinfunction "2_2") (pintype "passive"))
      (node (ref "C6") (pin "2") (pinfunction "2_2") (pintype "passive"))
      (node (ref "C7") (pin "1") (pinfunction "1_1") (pintype "passive"))
      (node (ref "C8") (pin "1") (pinfunction "1_1") (pintype "passive"))
      (node (ref "C9") (pin "2") (pinfunction "2_2") (pintype "passive"))
      (node (ref "J2") (pin "5") (pinfunction "5_5") (pintype "passive"))
      (node (ref "J2") (pin "6") (pinfunction "6_6") (pintype "passive"))
      (node (ref "J3") (pin "19") (pinfunction "19_19") (pintype "passive"))
      (node (ref "J3") (pin "20") (pinfunction "20_20") (pintype "passive"))
      (node (ref "J3") (pin "21") (pinfunction "21_21") (pintype "passive"))
      (node (ref "J3") (pin "22") (pinfunction "22_22") (pintype "passive"))
      (node (ref "J3") (pin "7") (pinfunction "7_7") (pintype "passive"))
      (node (ref "J3") (pin "8") (pinfunction "8_8") (pintype "passive"))
      (node (ref "J4") (pin "32") (pinfunction "32_32") (pintype "passive"))
      (node (ref "J4") (pin "7") (pinfunction "7_7") (pintype "passive"))
      (node (ref "J5") (pin "6") (pinfunction "6_6") (pintype "passive"))
      (node (ref "J5") (pin "7") (pinfunction "7_7") (pintype "passive"))
      (node (ref "J7") (pin "4") (pinfunction "4_4") (pintype "passive"))
      (node (ref "P2") (pin "8") (pintype "passive"))
      (node (ref "P6") (pin "A1") (pinfunction "GND_A1") (pintype "bidirectional"))
      (node (ref "P6") (pin "B1") (pinfunction "GND_B1") (pintype "bidirectional"))
      (node (ref "P7") (pin "A1") (pinfunction "GND_A1") (pintype "bidirectional"))
      (node (ref "P7") (pin "B1") (pinfunction "GND_B1") (pintype "bidirectional"))
      (node (ref "P9") (pin "A1") (pinfunction "GND_A1") (pintype "bidirectional"))
      (node (ref "P9") (pin "B1") (pinfunction "GND_B1") (pintype "bidirectional"))
      (node (ref "PWR") (pin "2") (pinfunction "K_2") (pintype "passive"))
      (node (ref "R10") (pin "2") (pinfunction "2_2") (pintype "passive"))
      (node (ref "R11") (pin "2") (pinfunction "2_2") (pintype "passive"))
      (node (ref "R18") (pin "1") (pinfunction "1_1") (pintype "passive"))
      (node (ref "R21") (pin "1") (pinfunction "1_1") (pintype "passive"))
      (node (ref "R22") (pin "1") (pinfunction "1_1") (pintype "passive"))
      (node (ref "R25") (pin "1") (pinfunction "1_1") (pintype "passive"))
      (node (ref "R8") (pin "1") (pinfunction "1_1") (pintype "passive"))
      (node (ref "R9") (pin "1") (pinfunction "1_1") (pintype "passive"))
      (node (ref "S1") (pin "3") (pinfunction "B1_3") (pintype "passive"))
      (node (ref "S2") (pin "3") (pinfunction "B1_3") (pintype "passive"))
      (node (ref "S5") (pin "2") (pinfunction "2_2") (pintype "passive"))
      (node (ref "U1") (pin "1") (pinfunction "GND_1") (pintype "passive"))
      (node (ref "U2") (pin "12") (pinfunction "VSSA_12") (pintype "power_in"))
      (node (ref "U2") (pin "18") (pinfunction "VSS_4_18") (pintype "power_in"))
      (node (ref "U2") (pin "31") (pinfunction "VSS_1_31") (pintype "power_in"))
      (node (ref "U2") (pin "63") (pinfunction "VSS_3_63") (pintype "power_in"))
      (node (ref "U3") (pin "18") (pinfunction "VSS/GND_18") (pintype "power_in"))
    )
    (net (code "90") (name "Net-(D2-K)") (class "Default")
      (node (ref "D2") (pin "2") (pinfunction "K_2") (pintype "passive"))
      (node (ref "R13") (pin "2") (pinfunction "2_2") (pintype "passive"))
    )
    (net (code "91") (name "Net-(D3-K)") (class "Default")
      (node (ref "D3") (pin "2") (pinfunction "K_2") (pintype "passive"))
      (node (ref "R21") (pin "2") (pinfunction "2_2") (pintype "passive"))
    )
    (net (code "92") (name "Net-(J3-Pad6)") (class "Default")
      (node (ref "J3") (pin "6") (pinfunction "6_6") (pintype "passive"))
      (node (ref "R5") (pin "1") (pinfunction "1_1") (pintype "passive"))
    )
    (net (code "93") (name "Net-(J3-Pad10)") (class "Default")
      (node (ref "J3") (pin "10") (pinfunction "10_10") (pintype "passive"))
      (node (ref "J5") (pin "1") (pinfunction "1_1") (pintype "passive"))
    )
    (net (code "94") (name "Net-(LED1-A)") (class "Default")
      (node (ref "LED1") (pin "1") (pinfunction "A_1") (pintype "passive"))
      (node (ref "R2") (pin "2") (pinfunction "2_2") (pintype "passive"))
    )
    (net (code "95") (name "Net-(LED2-A)") (class "Default")
      (node (ref "LED2") (pin "1") (pinfunction "A_1") (pintype "passive"))
      (node (ref "R3") (pin "2") (pinfunction "2_2") (pintype "passive"))
    )
    (net (code "96") (name "Net-(P2-Pad9)") (class "Default")
      (node (ref "P2") (pin "9") (pintype "passive"))
      (node (ref "R28") (pin "2") (pintype "passive"))
    )
    (net (code "97") (name "Net-(P2-Pad12)") (class "Default")
      (node (ref "P2") (pin "12") (pintype "passive"))
      (node (ref "R29") (pin "2") (pintype "passive"))
    )
    (net (code "98") (name "Net-(P6-CC-PadA5)") (class "Default")
      (node (ref "P6") (pin "A5") (pinfunction "CC_A5") (pintype "bidirectional"))
      (node (ref "R18") (pin "2") (pinfunction "2_2") (pintype "passive"))
    )
    (net (code "99") (name "Net-(P6-CC-PadB5)") (class "Default")
      (node (ref "P6") (pin "B5") (pinfunction "CC_B5") (pintype "bidirectional"))
      (node (ref "R25") (pin "2") (pinfunction "2_2") (pintype "passive"))
    )
    (net (code "100") (name "Net-(P7-CC-PadA5)") (class "Default")
      (node (ref "P7") (pin "A5") (pinfunction "CC_A5") (pintype "bidirectional"))
      (node (ref "R8") (pin "2") (pinfunction "2_2") (pintype "passive"))
    )
    (net (code "101") (name "Net-(P7-CC-PadB5)") (class "Default")
      (node (ref "P7") (pin "B5") (pinfunction "CC_B5") (pintype "bidirectional"))
      (node (ref "R9") (pin "2") (pinfunction "2_2") (pintype "passive"))
    )
    (net (code "102") (name "Net-(P9-CC-PadA5)") (class "Default")
      (node (ref "P9") (pin "A5") (pinfunction "CC_A5") (pintype "bidirectional"))
      (node (ref "R10") (pin "1") (pinfunction "1_1") (pintype "passive"))
    )
    (net (code "103") (name "Net-(P9-CC-PadB5)") (class "Default")
      (node (ref "P9") (pin "B5") (pinfunction "CC_B5") (pintype "bidirectional"))
      (node (ref "R11") (pin "1") (pinfunction "1_1") (pintype "passive"))
    )
    (net (code "104") (name "Net-(PWR-A)") (class "Default")
      (node (ref "PWR") (pin "1") (pinfunction "A_1") (pintype "passive"))
      (node (ref "R1") (pin "1") (pinfunction "1_1") (pintype "passive"))
    )
    (net (code "105") (name "Net-(U1-VOUT)") (class "Default")
      (node (ref "C13") (pin "1") (pinfunction "1_1") (pintype "passive"))
      (node (ref "S3") (pin "1") (pinfunction "1_1") (pintype "passive"))
      (node (ref "U1") (pin "2") (pinfunction "VOUT_2") (pintype "passive"))
    )
    (net (code "106") (name "Net-(U2-VDD_2)") (class "Default")
      (node (ref "R16") (pin "2") (pinfunction "2_2") (pintype "passive"))
      (node (ref "U2") (pin "48") (pinfunction "VDD_2_48") (pintype "power_in"))
    )
    (net (code "107") (name "Net-(U2-VSS_2)") (class "Default")
      (node (ref "R22") (pin "2") (pinfunction "2_2") (pintype "passive"))
      (node (ref "U2") (pin "47") (pinfunction "VSS_2_47") (pintype "power_in"))
    )
    (net (code "108") (name "unconnected-(P2-Pad7)") (class "Default")
      (node (ref "P2") (pin "7") (pintype "passive"))
    )
    (net (code "109") (name "unconnected-(P6-RFU1-PadA8)") (class "Default")
      (node (ref "P6") (pin "A8") (pinfunction "RFU1_A8") (pintype "bidirectional+no_connect"))
    )
    (net (code "110") (name "unconnected-(P6-RFU1-PadB8)") (class "Default")
      (node (ref "P6") (pin "B8") (pinfunction "RFU1_B8") (pintype "bidirectional+no_connect"))
    )
    (net (code "111") (name "unconnected-(P7-RFU1-PadA8)") (class "Default")
      (node (ref "P7") (pin "A8") (pinfunction "RFU1_A8") (pintype "bidirectional+no_connect"))
    )
    (net (code "112") (name "unconnected-(P7-RFU1-PadB8)") (class "Default")
      (node (ref "P7") (pin "B8") (pinfunction "RFU1_B8") (pintype "bidirectional+no_connect"))
    )
    (net (code "113") (name "unconnected-(P9-RFU1-PadA8)") (class "Default")
      (node (ref "P9") (pin "A8") (pinfunction "RFU1_A8") (pintype "bidirectional+no_connect"))
    )
    (net (code "114") (name "unconnected-(P9-RFU1-PadB8)") (class "Default")
      (node (ref "P9") (pin "B8") (pinfunction "RFU1_B8") (pintype "bidirectional+no_connect"))
    )
    (net (code "115") (name "unconnected-(S1-A1-Pad4)") (class "Default")
      (node (ref "S1") (pin "4") (pinfunction "A1_4") (pintype "passive"))
    )
    (net (code "116") (name "unconnected-(S1-B0-Pad2)") (class "Default")
      (node (ref "S1") (pin "2") (pinfunction "B0_2") (pintype "passive"))
    )
    (net (code "117") (name "unconnected-(S2-A1-Pad4)") (class "Default")
      (node (ref "S2") (pin "4") (pinfunction "A1_4") (pintype "passive"))
    )
    (net (code "118") (name "unconnected-(S2-B0-Pad2)") (class "Default")
      (node (ref "S2") (pin "2") (pinfunction "B0_2") (pintype "passive"))
    )
    (net (code "119") (name "unconnected-(S3-Pad2)") (class "Default")
      (node (ref "S3") (pin "2") (pinfunction "2_2") (pintype "passive"))
    )
    (net (code "120") (name "unconnected-(U3-PA5{slash}UART1_CTS{slash}PA1_(no5V)-Pad2)") (class "Default")
      (node (ref "U3") (pin "2") (pinfunction "PA5/UART1_CTS/PA1_(no5V)_2") (pintype "bidirectional+no_connect"))
    )
    (net (code "121") (name "unconnected-(U3-PB12{slash}SPI2_NSS{slash}CAN2_RX-Pad5)") (class "Default")
      (node (ref "U3") (pin "5") (pinfunction "PB12/SPI2_NSS/CAN2_RX_5") (pintype "bidirectional+no_connect"))
    )
    (net (code "122") (name "unconnected-(U3-PB14{slash}SPI2_MISO{slash}UART3_RTS-Pad7)") (class "Default")
      (node (ref "U3") (pin "7") (pinfunction "PB14/SPI2_MISO/UART3_RTS_7") (pintype "bidirectional+no_connect"))
    )
    (net (code "123") (name "unconnected-(U3-PB15{slash}SPI2_MOSI{slash}UART1_TX-Pad8)") (class "Default")
      (node (ref "U3") (pin "8") (pinfunction "PB15/SPI2_MOSI/UART1_TX_8") (pintype "bidirectional+no_connect"))
    )
  )
)
